# Adafruit_QT_5-3V_Shifter.net
KiCad netlist of a schematic drawn in EAGLE
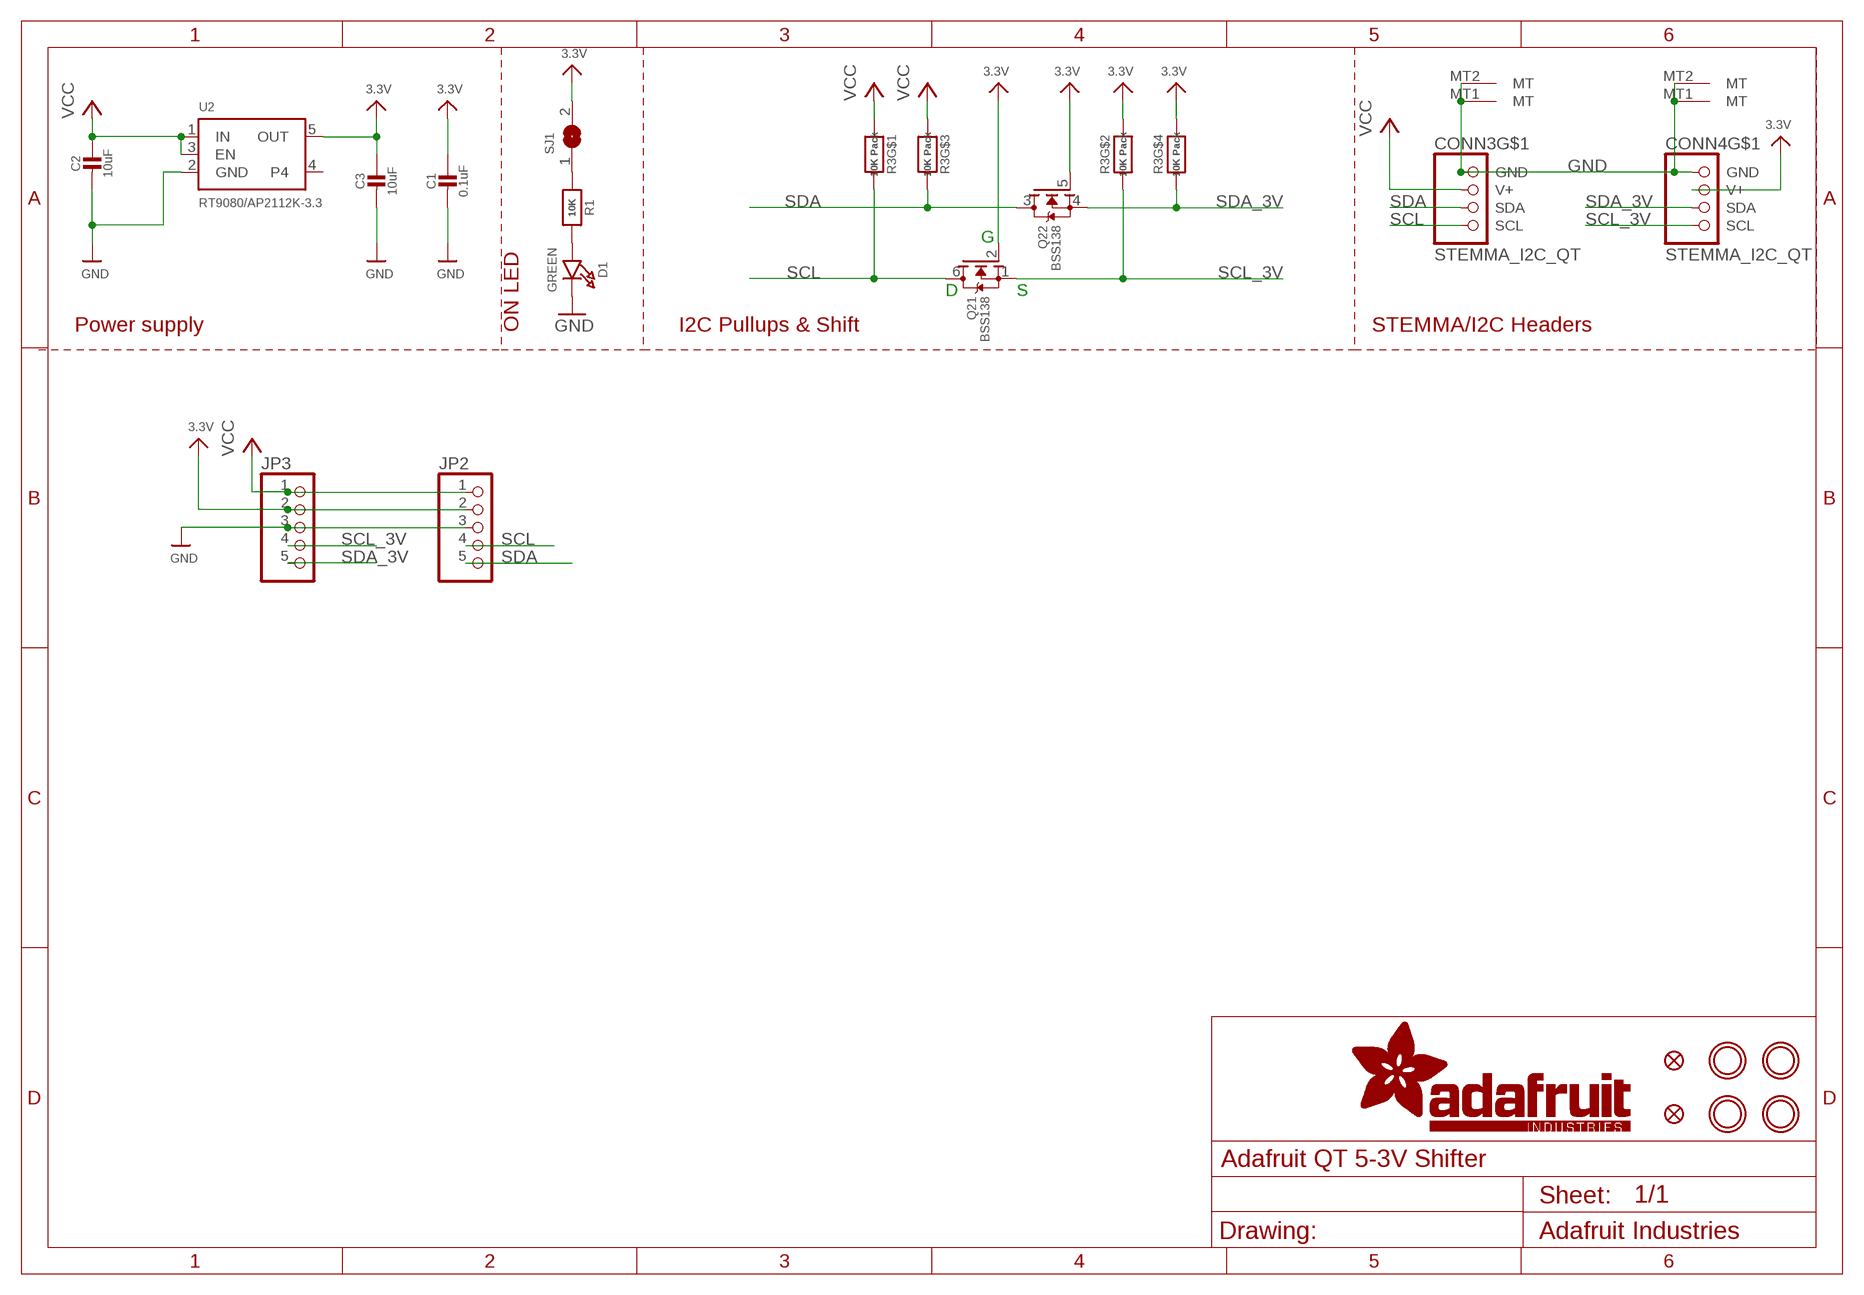
[diagram p0: schematic, sheet 1]

(export (version "E")
  (design (tool "Eeschema 10.0.6"))
  (components
    (comp (ref "C1")
      (value "0.1uF")
      (footprint "eagle-import:0603-NO")
      (libsource (lib "eagle-import") (part "CAP_CERAMIC0603_NO"))
    )
    (comp (ref "C2")
      (value "10uF")
      (footprint "eagle-import:0805-NO")
      (libsource (lib "eagle-import") (part "CAP_CERAMIC0805-NOOUTLINE"))
    )
    (comp (ref "C3")
      (value "10uF")
      (footprint "eagle-import:0805-NO")
      (libsource (lib "eagle-import") (part "CAP_CERAMIC0805-NOOUTLINE"))
    )
    (comp (ref "CONN3")
      (value "STEMMA_I2C_QT")
      (footprint "eagle-import:JST_SH4")
      (libsource (lib "eagle-import") (part "STEMMA_I2C_QT"))
    )
    (comp (ref "CONN4")
      (value "STEMMA_I2C_QT")
      (footprint "eagle-import:JST_SH4")
      (libsource (lib "eagle-import") (part "STEMMA_I2C_QT"))
    )
    (comp (ref "D1")
      (value "GREEN")
      (footprint "eagle-import:CHIPLED_0603_NOOUTLINE")
      (libsource (lib "eagle-import") (part "LED0603_NOOUTLINE"))
    )
    (comp (ref "FID3")
      (value "FIDUCIAL_1MM")
      (footprint "eagle-import:FIDUCIAL_1MM")
      (libsource (lib "eagle-import") (part "FIDUCIAL_1MM"))
    )
    (comp (ref "FID4")
      (value "FIDUCIAL_1MM")
      (footprint "eagle-import:FIDUCIAL_1MM")
      (libsource (lib "eagle-import") (part "FIDUCIAL_1MM"))
    )
    (comp (ref "JP2")
      (value "HEADER-1X576MIL")
      (footprint "eagle-import:1X05_ROUND_76")
      (libsource (lib "eagle-import") (part "HEADER-1X576MIL"))
    )
    (comp (ref "JP3")
      (value "HEADER-1X576MIL")
      (footprint "eagle-import:1X05_ROUND_76")
      (libsource (lib "eagle-import") (part "HEADER-1X576MIL"))
    )
    (comp (ref "Q2")
      (value "BSS138")
      (footprint "eagle-import:SOT363")
      (libsource (lib "eagle-import") (part "MOSFET-N_DUAL"))
    )
    (comp (ref "R1")
      (value "10K")
      (footprint "eagle-import:0603-NO")
      (libsource (lib "eagle-import") (part "RESISTOR_0603_NOOUT"))
    )
    (comp (ref "R3")
      (value "10K Pack")
      (footprint "eagle-import:RESPACK_4X0603")
      (libsource (lib "eagle-import") (part "RESISTOR_4PACK"))
    )
    (comp (ref "SJ1")
      (value "SOLDERJUMPERCLOSED")
      (footprint "eagle-import:SOLDERJUMPER_CLOSEDWIRE")
      (libsource (lib "eagle-import") (part "SOLDERJUMPERCLOSED"))
    )
    (comp (ref "U$1")
      (value "MOUNTINGHOLE2.5")
      (footprint "eagle-import:MOUNTINGHOLE_2.5_PLATED")
      (libsource (lib "eagle-import") (part "MOUNTINGHOLE2.5"))
    )
    (comp (ref "U$17")
      (value "MOUNTINGHOLE2.5")
      (footprint "eagle-import:MOUNTINGHOLE_2.5_PLATED")
      (libsource (lib "eagle-import") (part "MOUNTINGHOLE2.5"))
    )
    (comp (ref "U$19")
      (value "MOUNTINGHOLE2.5")
      (footprint "eagle-import:MOUNTINGHOLE_2.5_PLATED")
      (libsource (lib "eagle-import") (part "MOUNTINGHOLE2.5"))
    )
    (comp (ref "U$21")
      (value "MOUNTINGHOLE2.5")
      (footprint "eagle-import:MOUNTINGHOLE_2.5_PLATED")
      (libsource (lib "eagle-import") (part "MOUNTINGHOLE2.5"))
    )
    (comp (ref "U2")
      (value "RT9080/AP2112K-3.3")
      (footprint "eagle-import:SOT23-5")
      (fields (field (name "JLC_ROTATION") "0"))
      (libsource (lib "eagle-import") (part "VREG_SOT23-5"))
    )
  )
  (nets
    (net (code "1") (name "/SCL") (class "Default")
      (node (ref "CONN3") (pin "4") (pinfunction "SCL_4") (pintype "passive"))
      (node (ref "JP2") (pin "4") (pinfunction "4_4") (pintype "passive"))
      (node (ref "Q2") (pin "6") (pinfunction "D_6") (pintype "bidirectional"))
      (node (ref "R3") (pin "8") (pinfunction "2_8") (pintype "passive"))
    )
    (net (code "2") (name "/SCL_3V") (class "Default")
      (node (ref "CONN4") (pin "4") (pinfunction "SCL_4") (pintype "passive"))
      (node (ref "JP3") (pin "4") (pinfunction "4_4") (pintype "passive"))
      (node (ref "Q2") (pin "1") (pinfunction "S_1") (pintype "bidirectional"))
      (node (ref "R3") (pin "7") (pinfunction "2_7") (pintype "passive"))
    )
    (net (code "3") (name "/SDA") (class "Default")
      (node (ref "CONN3") (pin "3") (pinfunction "SDA_3") (pintype "passive"))
      (node (ref "JP2") (pin "5") (pinfunction "5_5") (pintype "passive"))
      (node (ref "Q2") (pin "3") (pinfunction "D_3") (pintype "bidirectional"))
      (node (ref "R3") (pin "6") (pinfunction "2_6") (pintype "passive"))
    )
    (net (code "4") (name "/SDA_3V") (class "Default")
      (node (ref "CONN4") (pin "3") (pinfunction "SDA_3") (pintype "passive"))
      (node (ref "JP3") (pin "5") (pinfunction "5_5") (pintype "passive"))
      (node (ref "Q2") (pin "4") (pinfunction "S_4") (pintype "bidirectional"))
      (node (ref "R3") (pin "5") (pinfunction "2_5") (pintype "passive"))
    )
    (net (code "5") (name "3.3V") (class "Default")
      (node (ref "C1") (pin "1") (pinfunction "1_1") (pintype "passive"))
      (node (ref "C3") (pin "1") (pinfunction "1_1") (pintype "passive"))
      (node (ref "CONN4") (pin "2") (pinfunction "V+_2") (pintype "passive"))
      (node (ref "JP2") (pin "2") (pinfunction "2_2") (pintype "passive"))
      (node (ref "JP3") (pin "2") (pinfunction "2_2") (pintype "passive"))
      (node (ref "Q2") (pin "2") (pinfunction "G_2") (pintype "bidirectional"))
      (node (ref "Q2") (pin "5") (pinfunction "G_5") (pintype "bidirectional"))
      (node (ref "R3") (pin "2") (pinfunction "1_2") (pintype "passive"))
      (node (ref "R3") (pin "4") (pinfunction "1_4") (pintype "passive"))
      (node (ref "SJ1") (pin "2") (pinfunction "2_2") (pintype "passive"))
      (node (ref "U2") (pin "5") (pinfunction "OUT_5") (pintype "power_in"))
    )
    (net (code "6") (name "GND") (class "Default")
      (node (ref "C1") (pin "2") (pinfunction "2_2") (pintype "passive"))
      (node (ref "C2") (pin "2") (pinfunction "2_2") (pintype "passive"))
      (node (ref "C3") (pin "2") (pinfunction "2_2") (pintype "passive"))
      (node (ref "CONN3") (pin "1") (pinfunction "GND_1") (pintype "passive"))
      (node (ref "CONN3") (pin "MT1") (pinfunction "MT_MT1") (pintype "bidirectional"))
      (node (ref "CONN3") (pin "MT2") (pinfunction "MT_MT2") (pintype "bidirectional"))
      (node (ref "CONN4") (pin "1") (pinfunction "GND_1") (pintype "passive"))
      (node (ref "CONN4") (pin "MT1") (pinfunction "MT_MT1") (pintype "bidirectional"))
      (node (ref "CONN4") (pin "MT2") (pinfunction "MT_MT2") (pintype "bidirectional"))
      (node (ref "D1") (pin "C") (pinfunction "C_C") (pintype "passive"))
      (node (ref "JP2") (pin "3") (pinfunction "3_3") (pintype "passive"))
      (node (ref "JP3") (pin "3") (pinfunction "3_3") (pintype "passive"))
      (node (ref "U2") (pin "2") (pinfunction "GND_2") (pintype "power_in"))
    )
    (net (code "7") (name "Net-(D1-PadA)") (class "Default")
      (node (ref "D1") (pin "A") (pinfunction "A_A") (pintype "passive"))
      (node (ref "R1") (pin "2") (pinfunction "2_2") (pintype "passive"))
    )
    (net (code "8") (name "Net-(R1-Pad1)") (class "Default")
      (node (ref "R1") (pin "1") (pinfunction "1_1") (pintype "passive"))
      (node (ref "SJ1") (pin "1") (pinfunction "1_1") (pintype "passive"))
    )
    (net (code "9") (name "VCC") (class "Default")
      (node (ref "C2") (pin "1") (pinfunction "1_1") (pintype "passive"))
      (node (ref "CONN3") (pin "2") (pinfunction "V+_2") (pintype "passive"))
      (node (ref "JP2") (pin "1") (pinfunction "1_1") (pintype "passive"))
      (node (ref "JP3") (pin "1") (pinfunction "1_1") (pintype "passive"))
      (node (ref "R3") (pin "1") (pinfunction "1_1") (pintype "passive"))
      (node (ref "R3") (pin "3") (pinfunction "1_3") (pintype "passive"))
      (node (ref "U2") (pin "1") (pinfunction "IN_1") (pintype "power_in"))
      (node (ref "U2") (pin "3") (pinfunction "EN_3") (pintype "input"))
    )
    (net (code "10") (name "unconnected-(U2-P4-Pad4)") (class "Default")
      (node (ref "U2") (pin "4") (pinfunction "P4_4") (pintype "bidirectional"))
    )
  )
)
